# GIT_TEST.net
KiCad netlist of a schematic drawn in Altium Designer
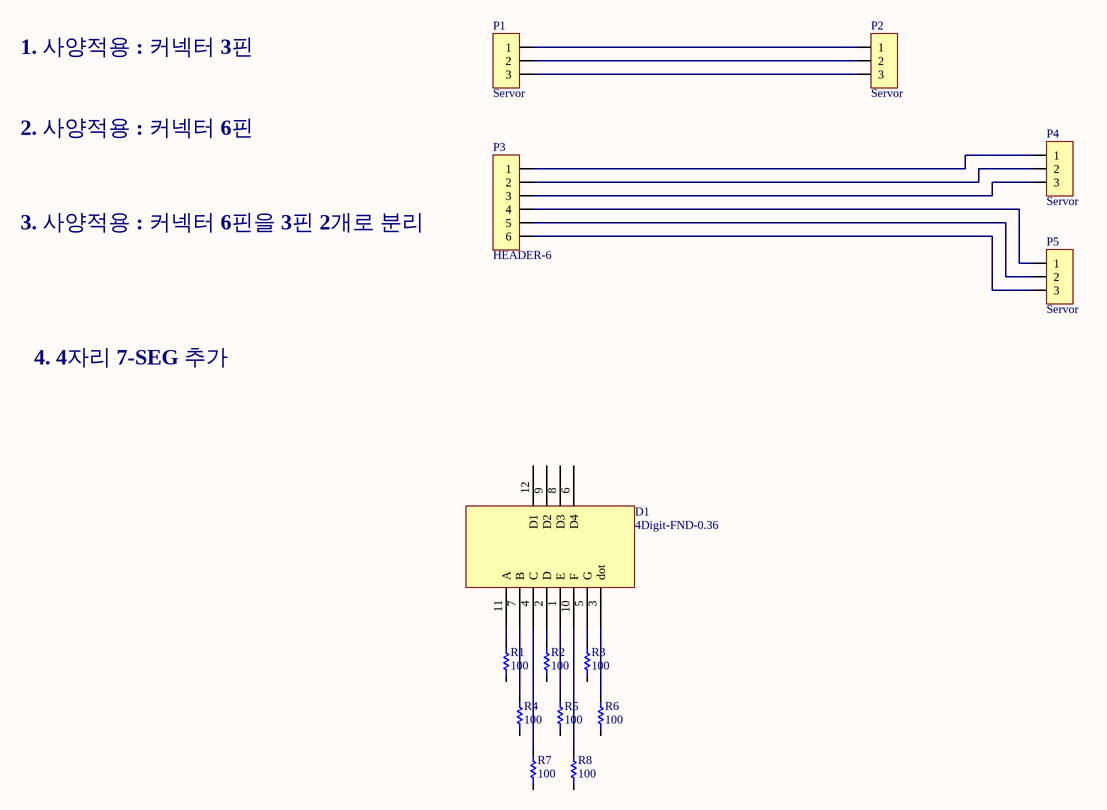
[diagram p0: GIT_TEST.SchDoc]

(export (version "E")
  (design (tool "Eeschema 10.0.6"))
  (components
    (comp (ref "D1")
      (value "4Digit-FND-0.36")
      (footprint "4Digit-FND-0.36")
      (libsource (lib "bumble_1") (part "4Digit-FND-0.36"))
    )
    (comp (ref "P1")
      (value "Servor")
      (footprint "PIN3")
      (description "Connector")
      (libsource (lib "") (part "HEADER-3_1"))
    )
    (comp (ref "P2")
      (value "Servor")
      (footprint "PIN3")
      (description "Connector")
      (libsource (lib "bumble_1") (part "HEADER-3"))
    )
    (comp (ref "P3")
      (value "HEADER-6")
      (footprint "PIN6")
      (description "Connector")
      (libsource (lib "bumble_1") (part "HEADER-6"))
    )
    (comp (ref "P4")
      (value "Servor")
      (footprint "PIN3")
      (description "Connector")
      (libsource (lib "bumble_1") (part "HEADER-3"))
    )
    (comp (ref "P5")
      (value "Servor")
      (footprint "PIN3")
      (description "Connector")
      (libsource (lib "bumble_1") (part "HEADER-3"))
    )
    (comp (ref "R1")
      (value "100")
      (footprint "0603R1608")
      (description "Resistor")
      (fields (field (name "PUBLISHER") "Altium Limited"))
      (libsource (lib "bumble_1") (part "Res1_1"))
    )
    (comp (ref "R2")
      (value "100")
      (footprint "0603R1608")
      (description "Resistor")
      (fields (field (name "PUBLISHER") "Altium Limited"))
      (libsource (lib "bumble_1") (part "Res1_1"))
    )
    (comp (ref "R3")
      (value "100")
      (footprint "0603R1608")
      (description "Resistor")
      (fields (field (name "PUBLISHER") "Altium Limited"))
      (libsource (lib "bumble_1") (part "Res1_1"))
    )
    (comp (ref "R4")
      (value "100")
      (footprint "0603R1608")
      (description "Resistor")
      (fields (field (name "PUBLISHER") "Altium Limited"))
      (libsource (lib "bumble_1") (part "Res1_1"))
    )
    (comp (ref "R5")
      (value "100")
      (footprint "0603R1608")
      (description "Resistor")
      (fields (field (name "PUBLISHER") "Altium Limited"))
      (libsource (lib "bumble_1") (part "Res1_1"))
    )
    (comp (ref "R6")
      (value "100")
      (footprint "0603R1608")
      (description "Resistor")
      (fields (field (name "PUBLISHER") "Altium Limited"))
      (libsource (lib "bumble_1") (part "Res1_1"))
    )
    (comp (ref "R7")
      (value "100")
      (footprint "0603R1608")
      (description "Resistor")
      (fields (field (name "PUBLISHER") "Altium Limited"))
      (libsource (lib "bumble_1") (part "Res1_1"))
    )
    (comp (ref "R8")
      (value "100")
      (footprint "0603R1608")
      (description "Resistor")
      (fields (field (name "PUBLISHER") "Altium Limited"))
      (libsource (lib "bumble_1") (part "Res1_1"))
    )
  )
  (nets
    (net (code "1") (name "Net-(D1-A)") (class "Default")
      (node (ref "D1") (pin "11") (pinfunction "A_11") (pintype "passive"))
      (node (ref "R1") (pin "2") (pinfunction "2_2") (pintype "passive"))
    )
    (net (code "2") (name "Net-(D1-B)") (class "Default")
      (node (ref "D1") (pin "7") (pinfunction "B_7") (pintype "passive"))
      (node (ref "R4") (pin "2") (pinfunction "2_2") (pintype "passive"))
    )
    (net (code "3") (name "Net-(D1-C)") (class "Default")
      (node (ref "D1") (pin "4") (pinfunction "C_4") (pintype "passive"))
      (node (ref "R7") (pin "2") (pinfunction "2_2") (pintype "passive"))
    )
    (net (code "4") (name "Net-(D1-D)") (class "Default")
      (node (ref "D1") (pin "2") (pinfunction "D_2") (pintype "passive"))
      (node (ref "R2") (pin "2") (pinfunction "2_2") (pintype "passive"))
    )
    (net (code "5") (name "Net-(D1-E)") (class "Default")
      (node (ref "D1") (pin "1") (pinfunction "E_1") (pintype "passive"))
      (node (ref "R5") (pin "2") (pinfunction "2_2") (pintype "passive"))
    )
    (net (code "6") (name "Net-(D1-F)") (class "Default")
      (node (ref "D1") (pin "10") (pinfunction "F_10") (pintype "passive"))
      (node (ref "R8") (pin "2") (pinfunction "2_2") (pintype "passive"))
    )
    (net (code "7") (name "Net-(D1-G)") (class "Default")
      (node (ref "D1") (pin "5") (pinfunction "G_5") (pintype "passive"))
      (node (ref "R3") (pin "2") (pinfunction "2_2") (pintype "passive"))
    )
    (net (code "8") (name "Net-(D1-dot)") (class "Default")
      (node (ref "D1") (pin "3") (pinfunction "dot_3") (pintype "passive"))
      (node (ref "R6") (pin "2") (pinfunction "2_2") (pintype "passive"))
    )
    (net (code "9") (name "Net-(P1-Pad1)") (class "Default")
      (node (ref "P1") (pin "1") (pinfunction "1_1") (pintype "passive"))
      (node (ref "P2") (pin "1") (pinfunction "1_1") (pintype "passive"))
    )
    (net (code "10") (name "Net-(P1-Pad2)") (class "Default")
      (node (ref "P1") (pin "2") (pinfunction "2_2") (pintype "passive"))
      (node (ref "P2") (pin "2") (pinfunction "2_2") (pintype "passive"))
    )
    (net (code "11") (name "Net-(P1-Pad3)") (class "Default")
      (node (ref "P1") (pin "3") (pinfunction "3_3") (pintype "passive"))
      (node (ref "P2") (pin "3") (pinfunction "3_3") (pintype "passive"))
    )
    (net (code "12") (name "Net-(P3-Pad1)") (class "Default")
      (node (ref "P3") (pin "1") (pinfunction "1_1") (pintype "passive"))
      (node (ref "P4") (pin "1") (pinfunction "1_1") (pintype "passive"))
    )
    (net (code "13") (name "Net-(P3-Pad2)") (class "Default")
      (node (ref "P3") (pin "2") (pinfunction "2_2") (pintype "passive"))
      (node (ref "P4") (pin "2") (pinfunction "2_2") (pintype "passive"))
    )
    (net (code "14") (name "Net-(P3-Pad3)") (class "Default")
      (node (ref "P3") (pin "3") (pinfunction "3_3") (pintype "passive"))
      (node (ref "P4") (pin "3") (pinfunction "3_3") (pintype "passive"))
    )
    (net (code "15") (name "Net-(P3-Pad4)") (class "Default")
      (node (ref "P3") (pin "4") (pinfunction "4_4") (pintype "passive"))
      (node (ref "P5") (pin "1") (pinfunction "1_1") (pintype "passive"))
    )
    (net (code "16") (name "Net-(P3-Pad5)") (class "Default")
      (node (ref "P3") (pin "5") (pinfunction "5_5") (pintype "passive"))
      (node (ref "P5") (pin "2") (pinfunction "2_2") (pintype "passive"))
    )
    (net (code "17") (name "Net-(P3-Pad6)") (class "Default")
      (node (ref "P3") (pin "6") (pinfunction "6_6") (pintype "passive"))
      (node (ref "P5") (pin "3") (pinfunction "3_3") (pintype "passive"))
    )
    (net (code "18") (name "unconnected-(D1-D1-Pad12)") (class "Default")
      (node (ref "D1") (pin "12") (pinfunction "D1_12") (pintype "passive"))
    )
    (net (code "19") (name "unconnected-(D1-D2-Pad9)") (class "Default")
      (node (ref "D1") (pin "9") (pinfunction "D2_9") (pintype "passive"))
    )
    (net (code "20") (name "unconnected-(D1-D3-Pad8)") (class "Default")
      (node (ref "D1") (pin "8") (pinfunction "D3_8") (pintype "passive"))
    )
    (net (code "21") (name "unconnected-(D1-D4-Pad6)") (class "Default")
      (node (ref "D1") (pin "6") (pinfunction "D4_6") (pintype "passive"))
    )
    (net (code "22") (name "unconnected-(R1-Pad1)") (class "Default")
      (node (ref "R1") (pin "1") (pinfunction "1_1") (pintype "passive"))
    )
    (net (code "23") (name "unconnected-(R2-Pad1)") (class "Default")
      (node (ref "R2") (pin "1") (pinfunction "1_1") (pintype "passive"))
    )
    (net (code "24") (name "unconnected-(R3-Pad1)") (class "Default")
      (node (ref "R3") (pin "1") (pinfunction "1_1") (pintype "passive"))
    )
    (net (code "25") (name "unconnected-(R4-Pad1)") (class "Default")
      (node (ref "R4") (pin "1") (pinfunction "1_1") (pintype "passive"))
    )
    (net (code "26") (name "unconnected-(R5-Pad1)") (class "Default")
      (node (ref "R5") (pin "1") (pinfunction "1_1") (pintype "passive"))
    )
    (net (code "27") (name "unconnected-(R6-Pad1)") (class "Default")
      (node (ref "R6") (pin "1") (pinfunction "1_1") (pintype "passive"))
    )
    (net (code "28") (name "unconnected-(R7-Pad1)") (class "Default")
      (node (ref "R7") (pin "1") (pinfunction "1_1") (pintype "passive"))
    )
    (net (code "29") (name "unconnected-(R8-Pad1)") (class "Default")
      (node (ref "R8") (pin "1") (pinfunction "1_1") (pintype "passive"))
    )
  )
)
